# Driver.net
KiCad netlist of a schematic drawn in Altium Designer
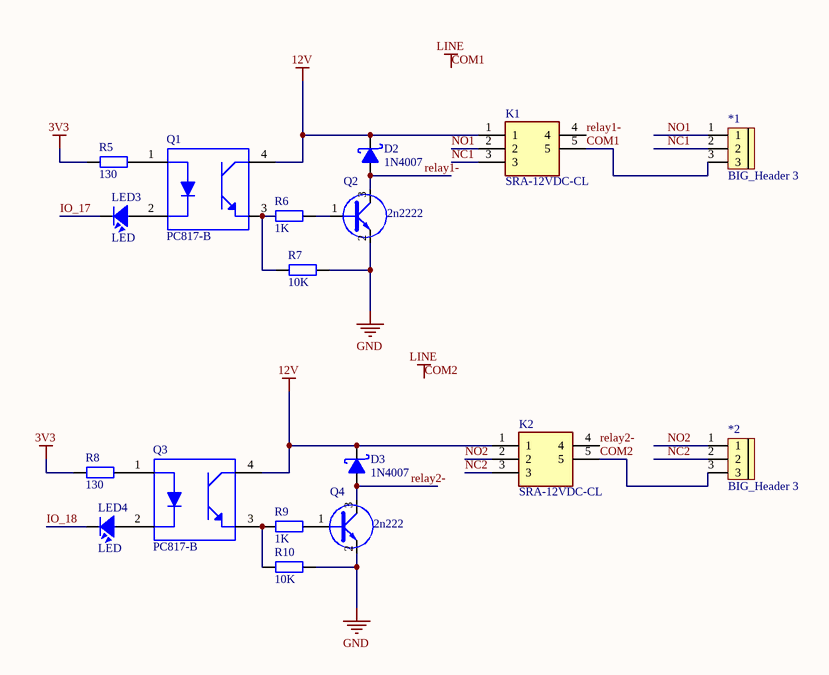
[diagram p0: Driver.SchDoc]

(export (version "E")
  (design (tool "Eeschema 10.0.6"))
  (components
    (comp (ref "*1")
      (value "BIG_Header 3")
      (footprint "KF-128_3P")
      (libsource (lib "Main") (part "BIG_Header 3"))
    )
    (comp (ref "*2")
      (value "BIG_Header 3")
      (footprint "KF-128_3P")
      (libsource (lib "Main") (part "BIG_Header 3"))
    )
    (comp (ref "D2")
      (value "1N4007")
      (footprint "SMA")
      (description "https://linhkien.cxt.vn/1119-1n4007-m7-diode-chinh-luu-1a-1000v-smado-214ac-10c.html")
      (libsource (lib "Main") (part "1N5822"))
    )
    (comp (ref "D3")
      (value "1N4007")
      (footprint "SMA")
      (description "https://linhkien.cxt.vn/1119-1n4007-m7-diode-chinh-luu-1a-1000v-smado-214ac-10c.html")
      (libsource (lib "Main") (part "1N5822"))
    )
    (comp (ref "K1")
      (value "SRA-12VDC-CL")
      (footprint "SamacSys:SRA12VDCCL")
      (description "https://linhkien.cxt.vn/3210-sra-12vdc-cl-songle-relay-20a-12vdc-5-chan.html")
      (libsource (lib "*") (part "SRA-12VDC-CL"))
    )
    (comp (ref "K2")
      (value "SRA-12VDC-CL")
      (footprint "SamacSys:SRA12VDCCL")
      (description "https://linhkien.cxt.vn/3210-sra-12vdc-cl-songle-relay-20a-12vdc-5-chan.html")
      (libsource (lib "*") (part "SRA-12VDC-CL"))
    )
    (comp (ref "LED3")
      (value "LED")
      (footprint "LED-0805-Green")
      (description "LED Single colour Green and Red")
      (libsource (lib "Main") (part "LED"))
    )
    (comp (ref "LED4")
      (value "LED")
      (footprint "LED-0805-Green")
      (description "LED Single colour Green and Red")
      (libsource (lib "Main") (part "LED"))
    )
    (comp (ref "Q1")
      (value "PC817-B")
      (footprint "DIP4/W0.3")
      (description "https://linhkien.cxt.vn/10328-pc817-dip4.html")
      (fields (field (name "MF") "American Bright"))
      (libsource (lib "PC817-B") (part "PC817-B"))
    )
    (comp (ref "Q2")
      (value "2n2222")
      (footprint "SOT23")
      (description "https://linhkien.cxt.vn/2040-2n2222-1p-npn-transistor-600ma-40v-sot-23-10c.html")
      (libsource (lib "Main") (part "C1815"))
    )
    (comp (ref "Q3")
      (value "PC817-B")
      (footprint "DIP4/W0.3")
      (description "https://linhkien.cxt.vn/10328-pc817-dip4.html")
      (fields (field (name "MF") "American Bright"))
      (libsource (lib "PC817-B") (part "PC817-B"))
    )
    (comp (ref "Q4")
      (value "2n222")
      (footprint "SOT23")
      (description "https://linhkien.cxt.vn/2040-2n2222-1p-npn-transistor-600ma-40v-sot-23-10c.html")
      (libsource (lib "Main") (part "C1815"))
    )
    (comp (ref "R5")
      (value "130")
      (footprint "RES-SMD-0805")
      (description "https://linhkien.cxt.vn/2109-dien-tro-130r-0805-5-50c.html")
      (fields
        (field (name "MANUFACTURER") "Generic Components")
        (field (name "PUBLISHER") "Altium Hobart Technology Centre")
      )
      (libsource (lib "Main") (part "Resistor - SMD"))
    )
    (comp (ref "R6")
      (value "1K")
      (footprint "RES-SMD-0805")
      (description "https://linhkien.cxt.vn/6152-dien-tro-174k-0805-1-50c.html")
      (fields
        (field (name "MANUFACTURER") "Generic Components")
        (field (name "PUBLISHER") "Altium Hobart Technology Centre")
      )
      (libsource (lib "Main") (part "Resistor - SMD"))
    )
    (comp (ref "R7")
      (value "10K")
      (footprint "RES-SMD-0805")
      (description "Resistor SMD")
      (fields
        (field (name "MANUFACTURER") "Generic Components")
        (field (name "PUBLISHER") "Altium Hobart Technology Centre")
      )
      (libsource (lib "Main") (part "Resistor - SMD"))
    )
    (comp (ref "R8")
      (value "130")
      (footprint "RES-SMD-0805")
      (description "https://linhkien.cxt.vn/2109-dien-tro-130r-0805-5-50c.html")
      (fields
        (field (name "MANUFACTURER") "Generic Components")
        (field (name "PUBLISHER") "Altium Hobart Technology Centre")
      )
      (libsource (lib "Main") (part "Resistor - SMD"))
    )
    (comp (ref "R9")
      (value "1K")
      (footprint "RES-SMD-0805")
      (description "https://linhkien.cxt.vn/6152-dien-tro-174k-0805-1-50c.html")
      (fields
        (field (name "MANUFACTURER") "Generic Components")
        (field (name "PUBLISHER") "Altium Hobart Technology Centre")
      )
      (libsource (lib "Main") (part "Resistor - SMD"))
    )
    (comp (ref "R10")
      (value "10K")
      (footprint "RES-SMD-0805")
      (description "17.4K")
      (fields
        (field (name "MANUFACTURER") "Generic Components")
        (field (name "PUBLISHER") "Altium Hobart Technology Centre")
      )
      (libsource (lib "Main") (part "Resistor - SMD"))
    )
  )
  (nets
    (net (code "1") (name "/IO_17") (class "Default")
      (node (ref "LED3") (pin "2") (pinfunction "2_2") (pintype "passive"))
    )
    (net (code "2") (name "/IO_18") (class "Default")
      (node (ref "LED4") (pin "2") (pinfunction "2_2") (pintype "passive"))
    )
    (net (code "3") (name "/NC1") (class "Default")
      (node (ref "*1") (pin "2") (pinfunction "2_2") (pintype "passive"))
      (node (ref "K1") (pin "3") (pinfunction "3_3") (pintype "passive"))
    )
    (net (code "4") (name "/NC2") (class "Default")
      (node (ref "*2") (pin "2") (pinfunction "2_2") (pintype "passive"))
      (node (ref "K2") (pin "3") (pinfunction "3_3") (pintype "passive"))
    )
    (net (code "5") (name "/NO1") (class "Default")
      (node (ref "*1") (pin "1") (pinfunction "1_1") (pintype "passive"))
      (node (ref "K1") (pin "2") (pinfunction "2_2") (pintype "passive"))
    )
    (net (code "6") (name "/NO2") (class "Default")
      (node (ref "*2") (pin "1") (pinfunction "1_1") (pintype "passive"))
      (node (ref "K2") (pin "2") (pinfunction "2_2") (pintype "passive"))
    )
    (net (code "7") (name "/relay1-") (class "Default")
      (node (ref "D2") (pin "1") (pinfunction "A_1") (pintype "passive"))
      (node (ref "K1") (pin "4") (pinfunction "4_4") (pintype "passive"))
      (node (ref "Q2") (pin "3") (pinfunction "C_3") (pintype "passive"))
    )
    (net (code "8") (name "/relay2-") (class "Default")
      (node (ref "D3") (pin "1") (pinfunction "A_1") (pintype "passive"))
      (node (ref "K2") (pin "4") (pinfunction "4_4") (pintype "passive"))
      (node (ref "Q4") (pin "3") (pinfunction "C_3") (pintype "passive"))
    )
    (net (code "9") (name "3V3") (class "Default")
      (node (ref "R5") (pin "2") (pinfunction "2_2") (pintype "passive"))
      (node (ref "R8") (pin "2") (pinfunction "2_2") (pintype "passive"))
    )
    (net (code "10") (name "12V") (class "Default")
      (node (ref "D2") (pin "2") (pinfunction "K_2") (pintype "passive"))
      (node (ref "D3") (pin "2") (pinfunction "K_2") (pintype "passive"))
      (node (ref "K1") (pin "1") (pinfunction "1_1") (pintype "passive"))
      (node (ref "K2") (pin "1") (pinfunction "1_1") (pintype "passive"))
      (node (ref "Q1") (pin "4") (pinfunction "COLLECTOR_4") (pintype "passive"))
      (node (ref "Q3") (pin "4") (pinfunction "COLLECTOR_4") (pintype "passive"))
    )
    (net (code "11") (name "GND") (class "Default")
      (node (ref "Q2") (pin "2") (pinfunction "E_2") (pintype "passive"))
      (node (ref "Q4") (pin "2") (pinfunction "E_2") (pintype "passive"))
      (node (ref "R10") (pin "1") (pinfunction "1_1") (pintype "passive"))
      (node (ref "R7") (pin "1") (pinfunction "1_1") (pintype "passive"))
    )
    (net (code "12") (name "LINE") (class "Default")
      (node (ref "*1") (pin "3") (pinfunction "3_3") (pintype "passive"))
      (node (ref "*2") (pin "3") (pinfunction "3_3") (pintype "passive"))
      (node (ref "K1") (pin "5") (pinfunction "5_5") (pintype "passive"))
      (node (ref "K2") (pin "5") (pinfunction "5_5") (pintype "passive"))
    )
    (net (code "13") (name "Net-(Q1-ANODE)") (class "Default")
      (node (ref "Q1") (pin "1") (pinfunction "ANODE_1") (pintype "passive"))
      (node (ref "R5") (pin "1") (pinfunction "1_1") (pintype "passive"))
    )
    (net (code "14") (name "Net-(Q1-CATHODE)") (class "Default")
      (node (ref "LED3") (pin "1") (pinfunction "1_1") (pintype "passive"))
      (node (ref "Q1") (pin "2") (pinfunction "CATHODE_2") (pintype "passive"))
    )
    (net (code "15") (name "Net-(Q1-EMITTER)") (class "Default")
      (node (ref "Q1") (pin "3") (pinfunction "EMITTER_3") (pintype "passive"))
      (node (ref "R6") (pin "2") (pinfunction "2_2") (pintype "passive"))
      (node (ref "R7") (pin "2") (pinfunction "2_2") (pintype "passive"))
    )
    (net (code "16") (name "Net-(Q2-B)") (class "Default")
      (node (ref "Q2") (pin "1") (pinfunction "B_1") (pintype "passive"))
      (node (ref "R6") (pin "1") (pinfunction "1_1") (pintype "passive"))
    )
    (net (code "17") (name "Net-(Q3-ANODE)") (class "Default")
      (node (ref "Q3") (pin "1") (pinfunction "ANODE_1") (pintype "passive"))
      (node (ref "R8") (pin "1") (pinfunction "1_1") (pintype "passive"))
    )
    (net (code "18") (name "Net-(Q3-CATHODE)") (class "Default")
      (node (ref "LED4") (pin "1") (pinfunction "1_1") (pintype "passive"))
      (node (ref "Q3") (pin "2") (pinfunction "CATHODE_2") (pintype "passive"))
    )
    (net (code "19") (name "Net-(Q3-EMITTER)") (class "Default")
      (node (ref "Q3") (pin "3") (pinfunction "EMITTER_3") (pintype "passive"))
      (node (ref "R10") (pin "2") (pinfunction "2_2") (pintype "passive"))
      (node (ref "R9") (pin "2") (pinfunction "2_2") (pintype "passive"))
    )
    (net (code "20") (name "Net-(Q4-B)") (class "Default")
      (node (ref "Q4") (pin "1") (pinfunction "B_1") (pintype "passive"))
      (node (ref "R9") (pin "1") (pinfunction "1_1") (pintype "passive"))
    )
  )
)
